# motor12v.net
KiCad netlist of a schematic drawn in EAGLE
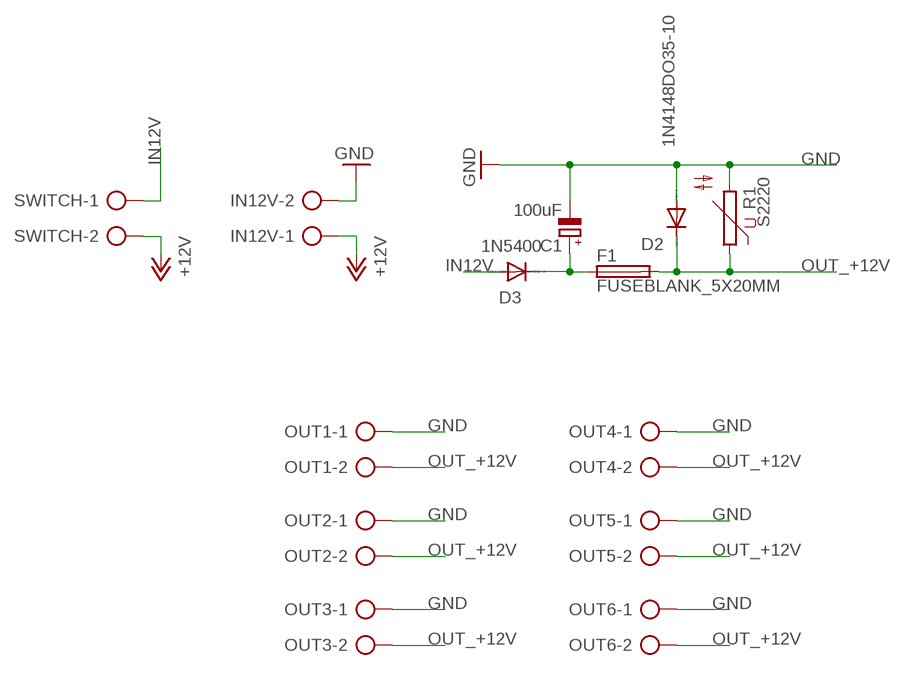
[diagram p0: schematic, sheet 1]

(export (version "E")
  (design (tool "Eeschema 10.0.6"))
  (components
    (comp (ref "C1")
      (value "100uF")
      (footprint "eagle-import:E3,5-8")
      (libsource (lib "eagle-import") (part "CPOL-EUE3.5-8"))
    )
    (comp (ref "D2")
      (value "1N4148DO35-10")
      (footprint "eagle-import:DO35-10")
      (libsource (lib "eagle-import") (part "1N4148DO35-10"))
    )
    (comp (ref "D3")
      (value "1N5400")
      (footprint "eagle-import:DO201-15")
      (libsource (lib "eagle-import") (part "1N5400"))
    )
    (comp (ref "F1")
      (value "FUSEBLANK_5X20MM")
      (footprint "eagle-import:FUSE_HOLDER_5X20MM")
      (libsource (lib "eagle-import") (part "FUSEBLANK_5X20MM"))
    )
    (comp (ref "IN12V")
      (value "AK500/2")
      (footprint "eagle-import:AK500_2")
      (libsource (lib "eagle-import") (part "AK500/2"))
    )
    (comp (ref "OUT1")
      (value "AK500/2")
      (footprint "eagle-import:AK500_2")
      (libsource (lib "eagle-import") (part "AK500/2"))
    )
    (comp (ref "OUT2")
      (value "AK500/2")
      (footprint "eagle-import:AK500_2")
      (libsource (lib "eagle-import") (part "AK500/2"))
    )
    (comp (ref "OUT3")
      (value "AK500/2")
      (footprint "eagle-import:AK500_2")
      (libsource (lib "eagle-import") (part "AK500/2"))
    )
    (comp (ref "OUT4")
      (value "AK500/2")
      (footprint "eagle-import:AK500_2")
      (libsource (lib "eagle-import") (part "AK500/2"))
    )
    (comp (ref "OUT5")
      (value "AK500/2")
      (footprint "eagle-import:AK500_2")
      (libsource (lib "eagle-import") (part "AK500/2"))
    )
    (comp (ref "OUT6")
      (value "AK500/2")
      (footprint "eagle-import:AK500_2")
      (libsource (lib "eagle-import") (part "AK500/2"))
    )
    (comp (ref "R1")
      (value "S2220")
      (footprint "eagle-import:S2220")
      (libsource (lib "eagle-import") (part "S2220"))
    )
    (comp (ref "SWITCH")
      (value "AK500/2")
      (footprint "eagle-import:AK500_2")
      (libsource (lib "eagle-import") (part "AK500/2"))
    )
  )
  (nets
    (net (code "1") (name "+12V") (class "Default")
      (node (ref "IN12V") (pin "1") (pinfunction "KL_1") (pintype "passive"))
      (node (ref "SWITCH") (pin "2") (pinfunction "KL_2") (pintype "passive"))
    )
    (net (code "2") (name "/IN12V") (class "Default")
      (node (ref "D3") (pin "A") (pinfunction "A_A") (pintype "passive"))
      (node (ref "SWITCH") (pin "1") (pinfunction "KL_1") (pintype "passive"))
    )
    (net (code "3") (name "/OUT_+12V") (class "Default")
      (node (ref "D2") (pin "C") (pinfunction "C_C") (pintype "passive"))
      (node (ref "F1") (pin "2") (pinfunction "2_2") (pintype "passive"))
      (node (ref "OUT1") (pin "2") (pinfunction "KL_2") (pintype "passive"))
      (node (ref "OUT2") (pin "2") (pinfunction "KL_2") (pintype "passive"))
      (node (ref "OUT3") (pin "2") (pinfunction "KL_2") (pintype "passive"))
      (node (ref "OUT4") (pin "2") (pinfunction "KL_2") (pintype "passive"))
      (node (ref "OUT5") (pin "2") (pinfunction "KL_2") (pintype "passive"))
      (node (ref "OUT6") (pin "2") (pinfunction "KL_2") (pintype "passive"))
      (node (ref "R1") (pin "1") (pinfunction "1_1") (pintype "passive"))
    )
    (net (code "4") (name "GND") (class "Default")
      (node (ref "C1") (pin "-") (pinfunction "-_-") (pintype "passive"))
      (node (ref "D2") (pin "A") (pinfunction "A_A") (pintype "passive"))
      (node (ref "IN12V") (pin "2") (pinfunction "KL_2") (pintype "passive"))
      (node (ref "OUT1") (pin "1") (pinfunction "KL_1") (pintype "passive"))
      (node (ref "OUT2") (pin "1") (pinfunction "KL_1") (pintype "passive"))
      (node (ref "OUT3") (pin "1") (pinfunction "KL_1") (pintype "passive"))
      (node (ref "OUT4") (pin "1") (pinfunction "KL_1") (pintype "passive"))
      (node (ref "OUT5") (pin "1") (pinfunction "KL_1") (pintype "passive"))
      (node (ref "OUT6") (pin "1") (pinfunction "KL_1") (pintype "passive"))
      (node (ref "R1") (pin "2") (pinfunction "2_2") (pintype "passive"))
    )
    (net (code "5") (name "Net-(C1-Pad+)") (class "Default")
      (node (ref "C1") (pin "+") (pinfunction "+_+") (pintype "passive"))
      (node (ref "D3") (pin "C") (pinfunction "C_C") (pintype "passive"))
      (node (ref "F1") (pin "1") (pinfunction "1_1") (pintype "passive"))
    )
  )
)
